# PowerSupply.net
KiCad netlist of a schematic drawn in Altium Designer
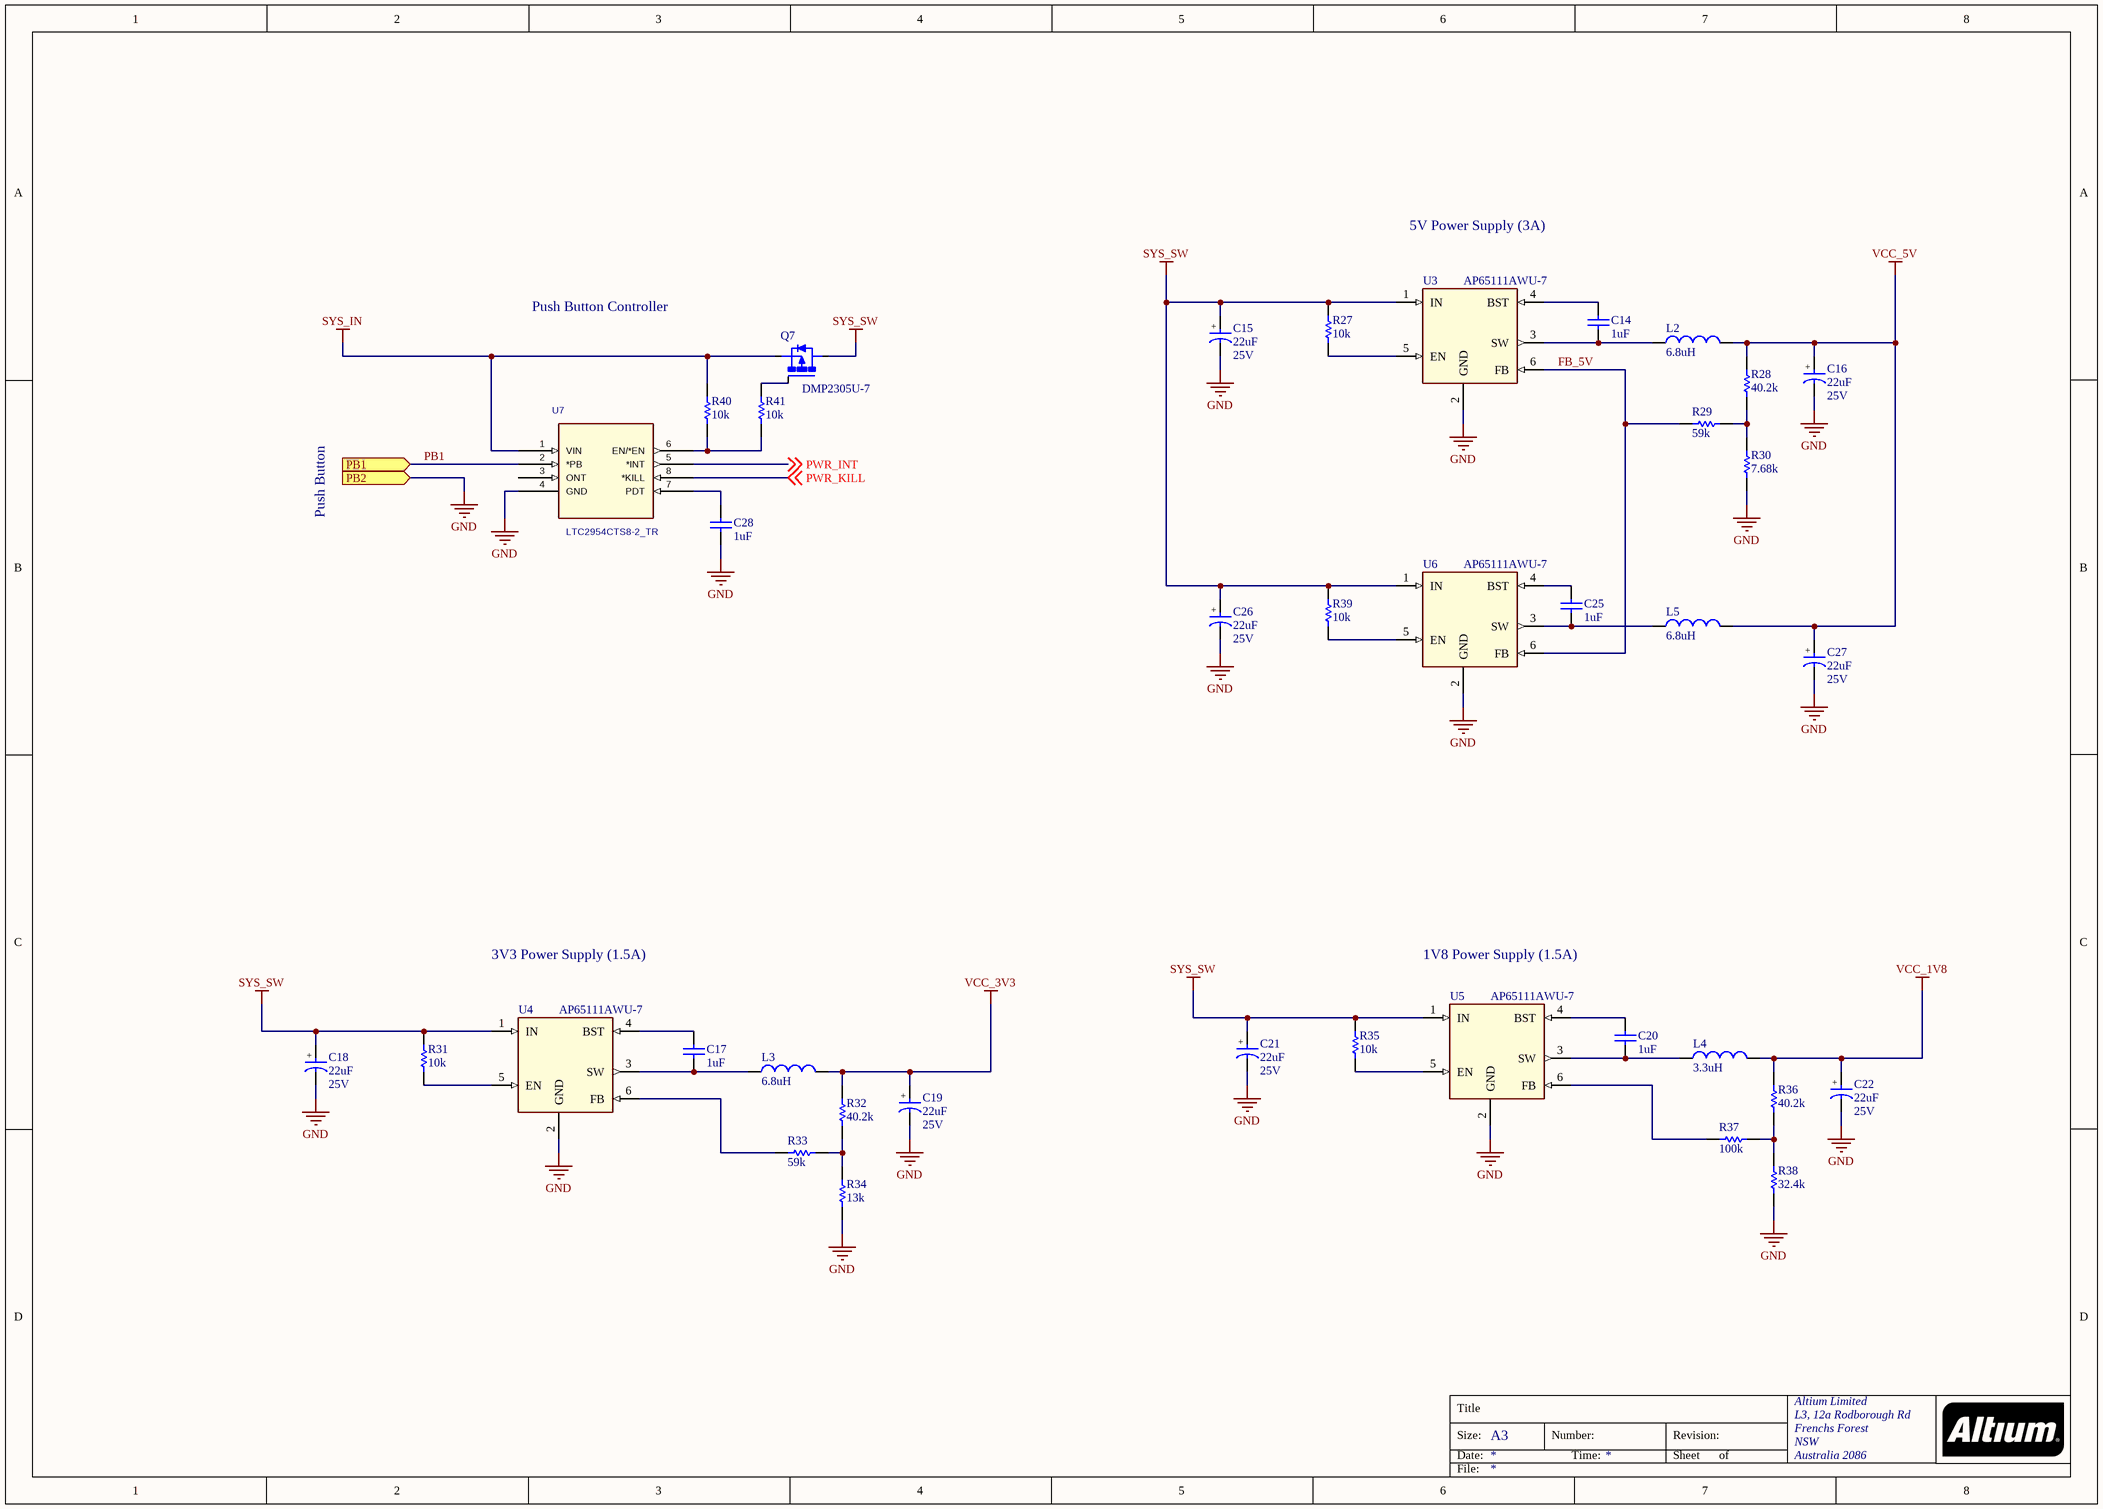
[diagram p0: PowerSupply.SchDoc]

(export (version "E")
  (design (tool "Eeschema 10.0.6"))
  (components
    (comp (ref "C14")
      (value "1uF")
      (footprint "C0603")
      (description "=Description")
      (fields (field (name "VOLTAGE") "25V") (field (name "Comment") "CAP"))
      (libsource (lib "DRClib") (part "CAP"))
    )
    (comp (ref "C15")
      (value "22uF")
      (footprint "CASE-A")
      (description "=Description")
      (fields (field (name "VOLTAGE") "25V") (field (name "Comment") "CAP-P"))
      (libsource (lib "DRClib") (part "CAP-P"))
    )
    (comp (ref "C16")
      (value "22uF")
      (footprint "CASE-A")
      (description "=Description")
      (fields (field (name "VOLTAGE") "25V") (field (name "Comment") "CAP-P"))
      (libsource (lib "DRClib") (part "CAP-P"))
    )
    (comp (ref "C17")
      (value "1uF")
      (footprint "C0603")
      (description "=Description")
      (fields (field (name "VOLTAGE") "25V") (field (name "Comment") "CAP"))
      (libsource (lib "DRClib") (part "CAP"))
    )
    (comp (ref "C18")
      (value "22uF")
      (footprint "CASE-A")
      (description "=Description")
      (fields (field (name "VOLTAGE") "25V") (field (name "Comment") "CAP-P"))
      (libsource (lib "DRClib") (part "CAP-P"))
    )
    (comp (ref "C19")
      (value "22uF")
      (footprint "CASE-A")
      (description "=Description")
      (fields (field (name "VOLTAGE") "25V") (field (name "Comment") "CAP-P"))
      (libsource (lib "DRClib") (part "CAP-P"))
    )
    (comp (ref "C20")
      (value "1uF")
      (footprint "C0603")
      (description "=Description")
      (fields (field (name "VOLTAGE") "25V") (field (name "Comment") "CAP"))
      (libsource (lib "DRClib") (part "CAP"))
    )
    (comp (ref "C21")
      (value "22uF")
      (footprint "CASE-A")
      (description "=Description")
      (fields (field (name "VOLTAGE") "25V") (field (name "Comment") "CAP-P"))
      (libsource (lib "DRClib") (part "CAP-P"))
    )
    (comp (ref "C22")
      (value "22uF")
      (footprint "CASE-A")
      (description "=Description")
      (fields (field (name "VOLTAGE") "25V") (field (name "Comment") "CAP-P"))
      (libsource (lib "DRClib") (part "CAP-P"))
    )
    (comp (ref "C25")
      (value "1uF")
      (footprint "C0603")
      (description "=Description")
      (fields (field (name "VOLTAGE") "25V") (field (name "Comment") "CAP"))
      (libsource (lib "DRClib") (part "CAP"))
    )
    (comp (ref "C26")
      (value "22uF")
      (footprint "CASE-A")
      (description "=Description")
      (fields (field (name "VOLTAGE") "25V") (field (name "Comment") "CAP-P"))
      (libsource (lib "DRClib") (part "CAP-P"))
    )
    (comp (ref "C27")
      (value "22uF")
      (footprint "CASE-A")
      (description "=Description")
      (fields (field (name "VOLTAGE") "25V") (field (name "Comment") "CAP-P"))
      (libsource (lib "DRClib") (part "CAP-P"))
    )
    (comp (ref "C28")
      (value "1uF")
      (footprint "C0402")
      (description "=Description")
      (fields (field (name "VOLTAGE") "25V") (field (name "Comment") "CAP"))
      (libsource (lib "DRClib") (part "CAP"))
    )
    (comp (ref "L2")
      (value "6.8uH")
      (footprint "PA4332.XXXNLT")
      (description "=Description")
      (fields (field (name "PART_NUMBER") "PA4332.682NLT") (field (name "Comment") "PA4332.103NLT"))
      (libsource (lib "DRClib") (part "IND"))
    )
    (comp (ref "L3")
      (value "6.8uH")
      (footprint "PA4332.XXXNLT")
      (description "=Description")
      (fields (field (name "PART_NUMBER") "PA4332.682NLT") (field (name "Comment") "PA4332.103NLT"))
      (libsource (lib "DRClib") (part "IND"))
    )
    (comp (ref "L4")
      (value "3.3uH")
      (footprint "PA4332.XXXNLT")
      (description "FIXED IND 10UH 2A 216 MOHM SMD")
      (fields (field (name "PART_NUMBER") "PA4332.332NLT") (field (name "Comment") "PA4332.103NLT"))
      (libsource (lib "DRClib") (part "IND"))
    )
    (comp (ref "L5")
      (value "6.8uH")
      (footprint "PA4332.XXXNLT")
      (description "=Description")
      (fields (field (name "PART_NUMBER") "PA4332.682NLT") (field (name "Comment") "PA4332.103NLT"))
      (libsource (lib "DRClib") (part "IND"))
    )
    (comp (ref "Q7")
      (value "DMP2305U-7")
      (footprint "SOT23-3")
      (description "P Channel MOSFET, SOT23")
      (libsource (lib "DRClib") (part "MOSFET_P_GSD"))
    )
    (comp (ref "R27")
      (value "10k")
      (footprint "R0402")
      (description "=Description")
      (fields (field (name "Comment") "RES"))
      (libsource (lib "DRClib") (part "RES"))
    )
    (comp (ref "R28")
      (value "40.2k")
      (footprint "R0402")
      (description "=Description")
      (fields (field (name "Comment") "RES"))
      (libsource (lib "DRClib") (part "RES"))
    )
    (comp (ref "R29")
      (value "59k")
      (footprint "R0402")
      (description "=Description")
      (fields (field (name "Comment") "RES"))
      (libsource (lib "DRClib") (part "RES"))
    )
    (comp (ref "R30")
      (value "7.68k")
      (footprint "R0402")
      (description "=Description")
      (fields (field (name "Comment") "RES"))
      (libsource (lib "DRClib") (part "RES"))
    )
    (comp (ref "R31")
      (value "10k")
      (footprint "R0402")
      (description "=Description")
      (fields (field (name "Comment") "RES"))
      (libsource (lib "DRClib") (part "RES"))
    )
    (comp (ref "R32")
      (value "40.2k")
      (footprint "R0402")
      (description "=Description")
      (fields (field (name "Comment") "RES"))
      (libsource (lib "DRClib") (part "RES"))
    )
    (comp (ref "R33")
      (value "59k")
      (footprint "R0402")
      (description "=Description")
      (fields (field (name "Comment") "RES"))
      (libsource (lib "DRClib") (part "RES"))
    )
    (comp (ref "R34")
      (value "13k")
      (footprint "R0402")
      (description "=Description")
      (fields (field (name "Comment") "RES"))
      (libsource (lib "DRClib") (part "RES"))
    )
    (comp (ref "R35")
      (value "10k")
      (footprint "R0402")
      (description "=Description")
      (fields (field (name "Comment") "RES"))
      (libsource (lib "DRClib") (part "RES"))
    )
    (comp (ref "R36")
      (value "40.2k")
      (footprint "R0402")
      (description "=Description")
      (fields (field (name "Comment") "RES"))
      (libsource (lib "DRClib") (part "RES"))
    )
    (comp (ref "R37")
      (value "100k")
      (footprint "R0402")
      (description "=Description")
      (fields (field (name "Comment") "RES"))
      (libsource (lib "DRClib") (part "RES"))
    )
    (comp (ref "R38")
      (value "32.4k")
      (footprint "R0402")
      (description "=Description")
      (fields (field (name "Comment") "RES"))
      (libsource (lib "DRClib") (part "RES"))
    )
    (comp (ref "R39")
      (value "10k")
      (footprint "R0402")
      (description "=Description")
      (fields (field (name "Comment") "RES"))
      (libsource (lib "DRClib") (part "RES"))
    )
    (comp (ref "R40")
      (value "10k")
      (footprint "R0402")
      (description "=Description")
      (fields (field (name "Comment") "RES"))
      (libsource (lib "DRClib") (part "RES"))
    )
    (comp (ref "R41")
      (value "10k")
      (footprint "R0402")
      (description "=Description")
      (fields (field (name "Comment") "RES"))
      (libsource (lib "DRClib") (part "RES"))
    )
    (comp (ref "U3")
      (value "AP65111AWU-7")
      (footprint "SOT95P280X100-6N")
      (description "Dcdc Conv Hv Buck Tsot26 t&r 3k")
      (fields (field (name "DIGI-KEY_PART_NUMBER") "AP65111AWU-7DICT-ND") (field (name "MF") "Diodes Inc."))
      (libsource (lib "DRClib") (part "AP65111AWU-7"))
    )
    (comp (ref "U4")
      (value "AP65111AWU-7")
      (footprint "SOT95P280X100-6N")
      (description "Dcdc Conv Hv Buck Tsot26 t&r 3k")
      (fields (field (name "DIGI-KEY_PART_NUMBER") "AP65111AWU-7DICT-ND") (field (name "MF") "Diodes Inc."))
      (libsource (lib "DRClib") (part "AP65111AWU-7"))
    )
    (comp (ref "U5")
      (value "AP65111AWU-7")
      (footprint "SOT95P280X100-6N")
      (description "Dcdc Conv Hv Buck Tsot26 t&r 3k")
      (fields (field (name "DIGI-KEY_PART_NUMBER") "AP65111AWU-7DICT-ND") (field (name "MF") "Diodes Inc."))
      (libsource (lib "DRClib") (part "AP65111AWU-7"))
    )
    (comp (ref "U6")
      (value "AP65111AWU-7")
      (footprint "SOT95P280X100-6N")
      (description "Dcdc Conv Hv Buck Tsot26 t&r 3k")
      (fields (field (name "DIGI-KEY_PART_NUMBER") "AP65111AWU-7DICT-ND") (field (name "MF") "Diodes Inc."))
      (libsource (lib "DRClib") (part "AP65111AWU-7"))
    )
    (comp (ref "U7")
      (value "LTC2954CTS8-2_TR")
      (footprint "TSOT-23_TS8-M")
      (fields (field (name "PART_NUMBER") "LTC2954CTS8-2#TRMPBF"))
      (libsource (lib "DRClib") (part "LTC2954CTS8-2_TR"))
    )
  )
  (nets
    (net (code "1") (name "/FB_5V") (class "Default")
      (node (ref "R29") (pin "1") (pinfunction "1_1") (pintype "passive"))
      (node (ref "U3") (pin "6") (pinfunction "FB_6") (pintype "input"))
      (node (ref "U6") (pin "6") (pinfunction "FB_6") (pintype "input"))
    )
    (net (code "2") (name "/PB1") (class "Default")
      (node (ref "U7") (pin "2") (pinfunction "*PB_2") (pintype "input"))
    )
    (net (code "3") (name "GND") (class "Default")
      (node (ref "C15") (pin "2") (pinfunction "2_2") (pintype "passive"))
      (node (ref "C16") (pin "2") (pinfunction "2_2") (pintype "passive"))
      (node (ref "C18") (pin "2") (pinfunction "2_2") (pintype "passive"))
      (node (ref "C19") (pin "2") (pinfunction "2_2") (pintype "passive"))
      (node (ref "C21") (pin "2") (pinfunction "2_2") (pintype "passive"))
      (node (ref "C22") (pin "2") (pinfunction "2_2") (pintype "passive"))
      (node (ref "C26") (pin "2") (pinfunction "2_2") (pintype "passive"))
      (node (ref "C27") (pin "2") (pinfunction "2_2") (pintype "passive"))
      (node (ref "C28") (pin "2") (pinfunction "2_2") (pintype "passive"))
      (node (ref "R30") (pin "2") (pinfunction "2_2") (pintype "passive"))
      (node (ref "R34") (pin "2") (pinfunction "2_2") (pintype "passive"))
      (node (ref "R38") (pin "2") (pinfunction "2_2") (pintype "passive"))
      (node (ref "U3") (pin "2") (pinfunction "GND_2") (pintype "power_in"))
      (node (ref "U4") (pin "2") (pinfunction "GND_2") (pintype "power_in"))
      (node (ref "U5") (pin "2") (pinfunction "GND_2") (pintype "power_in"))
      (node (ref "U6") (pin "2") (pinfunction "GND_2") (pintype "power_in"))
      (node (ref "U7") (pin "4") (pinfunction "GND_4") (pintype "power_in"))
    )
    (net (code "4") (name "Net-(Q7-G)") (class "Default")
      (node (ref "Q7") (pin "1") (pinfunction "G_1") (pintype "passive"))
      (node (ref "R41") (pin "2") (pinfunction "2_2") (pintype "passive"))
    )
    (net (code "5") (name "Net-(R28-Pad2)") (class "Default")
      (node (ref "R28") (pin "2") (pinfunction "2_2") (pintype "passive"))
      (node (ref "R29") (pin "2") (pinfunction "2_2") (pintype "passive"))
      (node (ref "R30") (pin "1") (pinfunction "1_1") (pintype "passive"))
    )
    (net (code "6") (name "Net-(R32-Pad2)") (class "Default")
      (node (ref "R32") (pin "2") (pinfunction "2_2") (pintype "passive"))
      (node (ref "R33") (pin "2") (pinfunction "2_2") (pintype "passive"))
      (node (ref "R34") (pin "1") (pinfunction "1_1") (pintype "passive"))
    )
    (net (code "7") (name "Net-(R36-Pad2)") (class "Default")
      (node (ref "R36") (pin "2") (pinfunction "2_2") (pintype "passive"))
      (node (ref "R37") (pin "2") (pinfunction "2_2") (pintype "passive"))
      (node (ref "R38") (pin "1") (pinfunction "1_1") (pintype "passive"))
    )
    (net (code "8") (name "Net-(U3-BST)") (class "Default")
      (node (ref "C14") (pin "1") (pinfunction "1_1") (pintype "passive"))
      (node (ref "U3") (pin "4") (pinfunction "BST_4") (pintype "input"))
    )
    (net (code "9") (name "Net-(U3-EN)") (class "Default")
      (node (ref "R27") (pin "2") (pinfunction "2_2") (pintype "passive"))
      (node (ref "U3") (pin "5") (pinfunction "EN_5") (pintype "input"))
    )
    (net (code "10") (name "Net-(U3-SW)") (class "Default")
      (node (ref "C14") (pin "2") (pinfunction "2_2") (pintype "passive"))
      (node (ref "L2") (pin "1") (pinfunction "1_1") (pintype "passive"))
      (node (ref "U3") (pin "3") (pinfunction "SW_3") (pintype "output"))
    )
    (net (code "11") (name "Net-(U4-BST)") (class "Default")
      (node (ref "C17") (pin "1") (pinfunction "1_1") (pintype "passive"))
      (node (ref "U4") (pin "4") (pinfunction "BST_4") (pintype "input"))
    )
    (net (code "12") (name "Net-(U4-EN)") (class "Default")
      (node (ref "R31") (pin "2") (pinfunction "2_2") (pintype "passive"))
      (node (ref "U4") (pin "5") (pinfunction "EN_5") (pintype "input"))
    )
    (net (code "13") (name "Net-(U4-FB)") (class "Default")
      (node (ref "R33") (pin "1") (pinfunction "1_1") (pintype "passive"))
      (node (ref "U4") (pin "6") (pinfunction "FB_6") (pintype "input"))
    )
    (net (code "14") (name "Net-(U4-SW)") (class "Default")
      (node (ref "C17") (pin "2") (pinfunction "2_2") (pintype "passive"))
      (node (ref "L3") (pin "1") (pinfunction "1_1") (pintype "passive"))
      (node (ref "U4") (pin "3") (pinfunction "SW_3") (pintype "output"))
    )
    (net (code "15") (name "Net-(U5-BST)") (class "Default")
      (node (ref "C20") (pin "1") (pinfunction "1_1") (pintype "passive"))
      (node (ref "U5") (pin "4") (pinfunction "BST_4") (pintype "input"))
    )
    (net (code "16") (name "Net-(U5-EN)") (class "Default")
      (node (ref "R35") (pin "2") (pinfunction "2_2") (pintype "passive"))
      (node (ref "U5") (pin "5") (pinfunction "EN_5") (pintype "input"))
    )
    (net (code "17") (name "Net-(U5-FB)") (class "Default")
      (node (ref "R37") (pin "1") (pinfunction "1_1") (pintype "passive"))
      (node (ref "U5") (pin "6") (pinfunction "FB_6") (pintype "input"))
    )
    (net (code "18") (name "Net-(U5-SW)") (class "Default")
      (node (ref "C20") (pin "2") (pinfunction "2_2") (pintype "passive"))
      (node (ref "L4") (pin "1") (pinfunction "1_1") (pintype "passive"))
      (node (ref "U5") (pin "3") (pinfunction "SW_3") (pintype "output"))
    )
    (net (code "19") (name "Net-(U6-BST)") (class "Default")
      (node (ref "C25") (pin "1") (pinfunction "1_1") (pintype "passive"))
      (node (ref "U6") (pin "4") (pinfunction "BST_4") (pintype "input"))
    )
    (net (code "20") (name "Net-(U6-EN)") (class "Default")
      (node (ref "R39") (pin "2") (pinfunction "2_2") (pintype "passive"))
      (node (ref "U6") (pin "5") (pinfunction "EN_5") (pintype "input"))
    )
    (net (code "21") (name "Net-(U6-SW)") (class "Default")
      (node (ref "C25") (pin "2") (pinfunction "2_2") (pintype "passive"))
      (node (ref "L5") (pin "1") (pinfunction "1_1") (pintype "passive"))
      (node (ref "U6") (pin "3") (pinfunction "SW_3") (pintype "output"))
    )
    (net (code "22") (name "Net-(U7-EN{slash}*EN)") (class "Default")
      (node (ref "R40") (pin "1") (pinfunction "1_1") (pintype "passive"))
      (node (ref "R41") (pin "1") (pinfunction "1_1") (pintype "passive"))
      (node (ref "U7") (pin "6") (pinfunction "EN/*EN_6") (pintype "output"))
    )
    (net (code "23") (name "Net-(U7-PDT)") (class "Default")
      (node (ref "C28") (pin "1") (pinfunction "1_1") (pintype "passive"))
      (node (ref "U7") (pin "7") (pinfunction "PDT_7") (pintype "input"))
    )
    (net (code "24") (name "PWR_INT") (class "Default")
      (node (ref "U7") (pin "5") (pinfunction "*INT_5") (pintype "output"))
    )
    (net (code "25") (name "PWR_KILL") (class "Default")
      (node (ref "U7") (pin "8") (pinfunction "*KILL_8") (pintype "input"))
    )
    (net (code "26") (name "SYS_IN") (class "Default")
      (node (ref "Q7") (pin "2") (pinfunction "S_2") (pintype "passive"))
      (node (ref "R40") (pin "2") (pinfunction "2_2") (pintype "passive"))
      (node (ref "U7") (pin "1") (pinfunction "VIN_1") (pintype "input"))
    )
    (net (code "27") (name "SYS_SW") (class "Default")
      (node (ref "C15") (pin "1") (pinfunction "1_1") (pintype "passive"))
      (node (ref "C18") (pin "1") (pinfunction "1_1") (pintype "passive"))
      (node (ref "C21") (pin "1") (pinfunction "1_1") (pintype "passive"))
      (node (ref "C26") (pin "1") (pinfunction "1_1") (pintype "passive"))
      (node (ref "Q7") (pin "3") (pinfunction "D_3") (pintype "passive"))
      (node (ref "R27") (pin "1") (pinfunction "1_1") (pintype "passive"))
      (node (ref "R31") (pin "1") (pinfunction "1_1") (pintype "passive"))
      (node (ref "R35") (pin "1") (pinfunction "1_1") (pintype "passive"))
      (node (ref "R39") (pin "1") (pinfunction "1_1") (pintype "passive"))
      (node (ref "U3") (pin "1") (pinfunction "IN_1") (pintype "input"))
      (node (ref "U4") (pin "1") (pinfunction "IN_1") (pintype "input"))
      (node (ref "U5") (pin "1") (pinfunction "IN_1") (pintype "input"))
      (node (ref "U6") (pin "1") (pinfunction "IN_1") (pintype "input"))
    )
    (net (code "28") (name "VCC_1V8") (class "Default")
      (node (ref "C22") (pin "1") (pinfunction "1_1") (pintype "passive"))
      (node (ref "L4") (pin "2") (pinfunction "2_2") (pintype "passive"))
      (node (ref "R36") (pin "1") (pinfunction "1_1") (pintype "passive"))
    )
    (net (code "29") (name "VCC_3V3") (class "Default")
      (node (ref "C19") (pin "1") (pinfunction "1_1") (pintype "passive"))
      (node (ref "L3") (pin "2") (pinfunction "2_2") (pintype "passive"))
      (node (ref "R32") (pin "1") (pinfunction "1_1") (pintype "passive"))
    )
    (net (code "30") (name "VCC_5V") (class "Default")
      (node (ref "C16") (pin "1") (pinfunction "1_1") (pintype "passive"))
      (node (ref "C27") (pin "1") (pinfunction "1_1") (pintype "passive"))
      (node (ref "L2") (pin "2") (pinfunction "2_2") (pintype "passive"))
      (node (ref "L5") (pin "2") (pinfunction "2_2") (pintype "passive"))
      (node (ref "R28") (pin "1") (pinfunction "1_1") (pintype "passive"))
    )
    (net (code "31") (name "unconnected-(U7-ONT-Pad3)") (class "Default")
      (node (ref "U7") (pin "3") (pinfunction "ONT_3") (pintype "input"))
    )
  )
)
